# AIL_Schem.net
KiCad netlist of a schematic drawn in Altium Designer
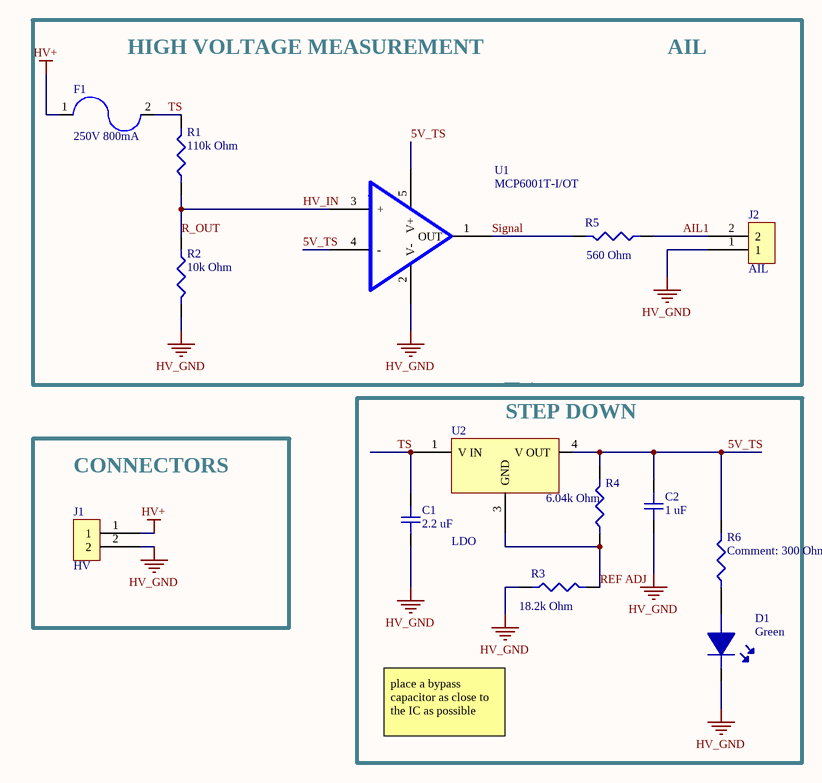
[diagram p0: AIL_Schem.SchDoc]

(export (version "E")
  (design (tool "Eeschema 10.0.6"))
  (components
    (comp (ref "C1")
      (value "2.2 uF")
      (footprint "CAPC5850X25N")
      (description "CAP CER 2.2UF 250V X7T 2220")
      (fields
        (field (name "MANUFACTURER") "TDK")
        (field (name "MANUFACTURER PART NUMBER") "CGA9P3X7T2E225K250KE")
      )
      (libsource (lib "TSAL_REV1") (part "CGA9P3X7T2E225K250KE"))
    )
    (comp (ref "C2")
      (value "1 uF")
      (footprint "CAPC2012X14N")
      (description "Cap Ceramic 1uF 10V X5R 10% SMD 0603 85C Paper T/R")
      (fields
        (field (name "MANUFACTURER") "Samsung")
        (field (name "MANUFACTURER PART NUMBER") "CL10A105KP8NNNC")
      )
      (libsource (lib "TSAL_REV1") (part "CL10A105KP8NNNC"))
    )
    (comp (ref "D1")
      (value "Green")
      (footprint "LED_0603")
      (description "LED Uni-Color Green 574nm 2-Pin Chip LED T/R")
      (fields
        (field (name "MANUFACTURER") "Vishay Lite-On")
        (field (name "MANUFACTURER PART NUMBER") "LTST-C191KGKT")
      )
      (libsource (lib "AIL") (part "LTST-C191KGKT"))
    )
    (comp (ref "F1")
      (value "250V 800mA")
      (footprint "FUSE_SMD")
      (fields (field (name "MANUFACTURER") "Bel") (field (name "MANUFACTURER PART NUMBER") "0678D0800-02"))
      (libsource (lib "TSAL_REV1") (part "0678D0800-02"))
    )
    (comp (ref "J1")
      (value "HV")
      (footprint "2_PIN_CONNECTOR")
      (fields (field (name "MANUFACTURER") "Molex") (field (name "MANUFACTURER PART NUMBER") "0705530001"))
      (libsource (lib "TSAL_REV1") (part "0705530001"))
    )
    (comp (ref "J2")
      (value "AIL")
      (footprint "2_PIN_CONNECTOR")
      (fields (field (name "MANUFACTURER") "Molex") (field (name "MANUFACTURER PART NUMBER") "0705530001"))
      (libsource (lib "AIL") (part "0705530001"))
    )
    (comp (ref "R1")
      (value "110k Ohm")
      (footprint "RESC3116X06N")
      (description "RES SMD 110K OHM 1% 1/4W 1206")
      (fields
        (field (name "MANUFACTURER") "Yageo")
        (field (name "MANUFACTURER PART NUMBER") "RC1206FR-07110KL")
      )
      (libsource (lib "TSAL_REV1") (part "RC1206FR-07110KL"))
    )
    (comp (ref "R2")
      (value "10k Ohm")
      (footprint "RESC2012X06N")
      (description "RES 10K OHM 1% 1/4W 0805")
      (fields
        (field (name "MANUFACTURER") "Stackpole Electronics")
        (field (name "MANUFACTURER PART NUMBER") "RNCP0805FTD10K0")
      )
      (libsource (lib "TSAL_REV1") (part "RNCP0805FTD10K0"))
    )
    (comp (ref "R3")
      (value "18.2k Ohm")
      (footprint "RESC2012X06N")
      (description "Panasonic ERA Series Thin Film Surface Mount Resistor 0805 Case 18.2k 0.1% 0.125W 25ppm/C")
      (fields
        (field (name "MANUFACTURER") "Panasonic")
        (field (name "MANUFACTURER PART NUMBER") "ERA-6AEB1822V")
      )
      (libsource (lib "TSAL_REV1") (part "ERA-6AEB1822V"))
    )
    (comp (ref "R4")
      (value "6.04k Ohm")
      (footprint "RESC2012X06N")
      (description "RES SMD 6.04KOHM 0.5% 1/10W 0805")
      (fields
        (field (name "MANUFACTURER") "Susumu")
        (field (name "MANUFACTURER PART NUMBER") "RR1220P-6041-D-M")
      )
      (libsource (lib "TSAL_REV1") (part "RR1220P-6041-D-M"))
    )
    (comp (ref "R5")
      (value "560 Ohm")
      (footprint "RESC2012X06N")
      (description "RES SMD 560 OHM 5% 0.4W 0805")
      (fields (field (name "MANUFACTURER") "Rohm") (field (name "MANUFACTURER PART NUMBER") "ESR10EZPJ561"))
      (libsource (lib "TSAL_REV1") (part "ESR10EZPJ561"))
    )
    (comp (ref "R6")
      (value "300 Ohm")
      (footprint "RESC1608X06N")
      (description "RES SMD 300 OHM 0.5% 1/16W 0603")
      (fields
        (field (name "MANUFACTURER") "Susumu")
        (field (name "MANUFACTURER PART NUMBER") "RR0816P-301-D")
      )
      (libsource (lib "TSAL_REV1") (part "RR0816P-301-D"))
    )
    (comp (ref "U1")
      (value "MCP6001T-I/OT")
      (description "MICROCHIP - MCP6001T-I/OT - OP AMP, 1MHZ, 0.6V/uS, SOT-23-5, FULL REEL")
      (fields (field (name "MANUFACTURER") "Microchip") (field (name "VOLTAGE") "6V"))
      (libsource (lib "AIL") (part "MCP6001T-I/OT"))
    )
    (comp (ref "U2")
      (value "LDO")
      (footprint "DPAK228P998X235-3N")
      (description "Standard Regulator Pos 1.2V to 440V 0.01A 3-Pin(2+Tab) TO-252")
      (fields (field (name "MANUFACTURER") "Microchip") (field (name "MANUFACTURER PART NUMBER") "LR8K4-G"))
      (libsource (lib "TSAL_REV1") (part "LR8K4-G"))
    )
  )
  (nets
    (net (code "1") (name "/5V_TS") (class "Default")
      (node (ref "C2") (pin "2") (pinfunction "2_2") (pintype "passive"))
      (node (ref "R4") (pin "2") (pinfunction "2_2") (pintype "passive"))
      (node (ref "R6") (pin "2") (pinfunction "2_2") (pintype "passive"))
      (node (ref "U1") (pin "4") (pinfunction "-_4") (pintype "passive"))
      (node (ref "U1") (pin "5") (pinfunction "V+_5") (pintype "passive"))
      (node (ref "U2") (pin "4") (pinfunction "V_OUT_4") (pintype "passive"))
    )
    (net (code "2") (name "/AIL1") (class "Default")
      (node (ref "J2") (pin "2") (pinfunction "2_2") (pintype "passive"))
      (node (ref "R5") (pin "1") (pinfunction "1_1") (pintype "passive"))
    )
    (net (code "3") (name "/HV_IN") (class "Default")
      (node (ref "R1") (pin "1") (pinfunction "1_1") (pintype "passive"))
      (node (ref "R2") (pin "1") (pinfunction "1_1") (pintype "passive"))
      (node (ref "U1") (pin "3") (pinfunction "+_3") (pintype "passive"))
    )
    (net (code "4") (name "/REF ADJ") (class "Default")
      (node (ref "R3") (pin "2") (pinfunction "2_2") (pintype "passive"))
      (node (ref "R4") (pin "1") (pinfunction "1_1") (pintype "passive"))
      (node (ref "U2") (pin "3") (pinfunction "GND_3") (pintype "passive"))
    )
    (net (code "5") (name "/Signal") (class "Default")
      (node (ref "R5") (pin "2") (pinfunction "2_2") (pintype "passive"))
      (node (ref "U1") (pin "1") (pinfunction "OUT_1") (pintype "passive"))
    )
    (net (code "6") (name "/TS") (class "Default")
      (node (ref "C1") (pin "2") (pinfunction "2_2") (pintype "passive"))
      (node (ref "F1") (pin "2") (pinfunction "2_2") (pintype "passive"))
      (node (ref "R1") (pin "2") (pinfunction "2_2") (pintype "passive"))
      (node (ref "U2") (pin "1") (pinfunction "V_IN_1") (pintype "passive"))
    )
    (net (code "7") (name "HV+") (class "Default")
      (node (ref "F1") (pin "1") (pinfunction "1_1") (pintype "passive"))
      (node (ref "J1") (pin "1") (pinfunction "1_1") (pintype "passive"))
    )
    (net (code "8") (name "HV_GND") (class "Default")
      (node (ref "C1") (pin "1") (pinfunction "1_1") (pintype "passive"))
      (node (ref "C2") (pin "1") (pinfunction "1_1") (pintype "passive"))
      (node (ref "D1") (pin "2") (pinfunction "2_2") (pintype "passive"))
      (node (ref "J1") (pin "2") (pinfunction "2_2") (pintype "passive"))
      (node (ref "J2") (pin "1") (pinfunction "1_1") (pintype "passive"))
      (node (ref "R2") (pin "2") (pinfunction "2_2") (pintype "passive"))
      (node (ref "R3") (pin "1") (pinfunction "1_1") (pintype "passive"))
      (node (ref "U1") (pin "2") (pinfunction "V-_2") (pintype "passive"))
    )
    (net (code "9") (name "Net-(D1-Pad1)") (class "Default")
      (node (ref "D1") (pin "1") (pinfunction "1_1") (pintype "passive"))
      (node (ref "R6") (pin "1") (pinfunction "1_1") (pintype "passive"))
    )
  )
)
